# power.net
KiCad netlist of a schematic drawn in Altium Designer
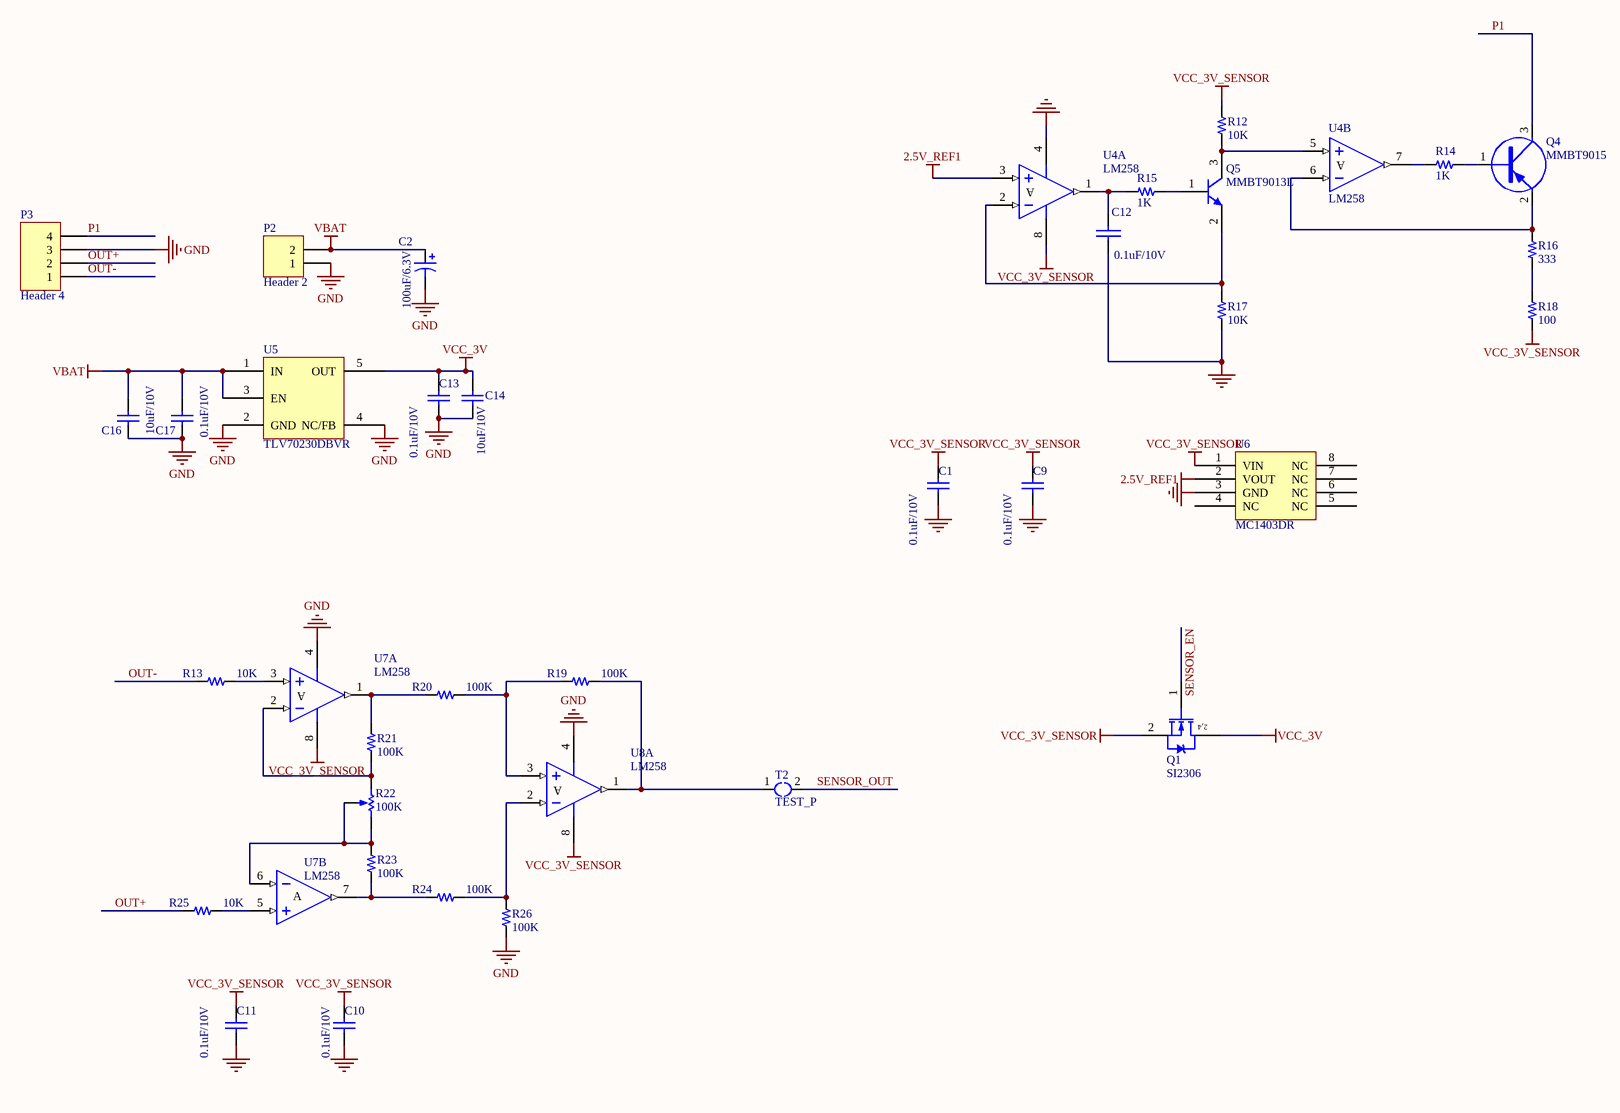
[diagram p0: power.SchDoc]

(export (version "E")
  (design (tool "Eeschema 10.0.6"))
  (components
    (comp (ref "C1")
      (value "0.1uF/10V")
      (footprint "0603C")
      (description "Capacitor")
      (fields (field (name "PUBLISHER") "Altium Limited"))
      (libsource (lib "Miscellaneous Devices") (part "Cap"))
    )
    (comp (ref "C2")
      (value "100uF/6.3V")
      (footprint "7343")
      (description "Polarized Capacitor (Radial)")
      (fields (field (name "PUBLISHER") "Altium Limited"))
      (libsource (lib "Miscellaneous Devices") (part "Cap Pol1"))
    )
    (comp (ref "C9")
      (value "0.1uF/10V")
      (footprint "0603C")
      (description "Capacitor")
      (fields (field (name "PUBLISHER") "Altium Limited"))
      (libsource (lib "Miscellaneous Devices") (part "Cap"))
    )
    (comp (ref "C10")
      (value "0.1uF/10V")
      (footprint "0603C")
      (description "Capacitor")
      (fields (field (name "PUBLISHER") "Altium Limited"))
      (libsource (lib "Miscellaneous Devices") (part "Cap"))
    )
    (comp (ref "C11")
      (value "0.1uF/10V")
      (footprint "0603C")
      (description "Capacitor")
      (fields (field (name "PUBLISHER") "Altium Limited"))
      (libsource (lib "Miscellaneous Devices") (part "Cap"))
    )
    (comp (ref "C12")
      (value "0.1uF/10V")
      (footprint "0603C")
      (description "Capacitor")
      (libsource (lib "*") (part "CAP"))
    )
    (comp (ref "C13")
      (value "0.1uF/10V")
      (footprint "0603C")
      (description "Capacitor")
      (fields (field (name "PUBLISHER") "Altium Limited"))
      (libsource (lib "Miscellaneous Devices") (part "Cap"))
    )
    (comp (ref "C14")
      (value "10uF/10V")
      (footprint "0603C")
      (description "Capacitor")
      (fields (field (name "PUBLISHER") "Altium Limited"))
      (libsource (lib "Miscellaneous Devices") (part "Cap"))
    )
    (comp (ref "C16")
      (value "10uF/10V")
      (footprint "0603C")
      (description "Capacitor")
      (fields (field (name "PUBLISHER") "Altium Limited"))
      (libsource (lib "Miscellaneous Devices") (part "Cap"))
    )
    (comp (ref "C17")
      (value "0.1uF/10V")
      (footprint "0603C")
      (description "Capacitor")
      (fields (field (name "PUBLISHER") "Altium Limited"))
      (libsource (lib "Miscellaneous Devices") (part "Cap"))
    )
    (comp (ref "P2")
      (value "Header 2")
      (footprint "2X2.54MM")
      (description "Header, 2-Pin")
      (fields (field (name "PUBLISHER") "Altium Limited"))
      (libsource (lib "Miscellaneous Connectors") (part "Header 2"))
    )
    (comp (ref "P3")
      (value "Header 4")
      (footprint "HDR1X4")
      (description "Header, 4-Pin")
      (fields (field (name "PUBLISHER") "Altium Limited"))
      (libsource (lib "Miscellaneous Connectors") (part "Header 4"))
    )
    (comp (ref "Q1")
      (value "SI2306")
      (footprint "SOT23-3")
      (description "BUK92150-55A")
      (fields (field (name "PUBLISHER") "Altium Limited"))
      (libsource (lib "Schlib1") (part "BUK92150-55A"))
    )
    (comp (ref "Q4") (value "MMBT9015") (footprint "SOT23-3") (libsource (lib "Schlib1") (part "PNP")))
    (comp (ref "Q5") (value "MMBT9013L") (footprint "SOT23-3") (libsource (lib "Schlib1") (part "NPN")))
    (comp (ref "R12")
      (value "10K")
      (footprint "0603R")
      (description "R")
      (libsource (lib "JRJ_1") (part "R"))
    )
    (comp (ref "R13")
      (value "10K")
      (footprint "0603R")
      (description "R")
      (libsource (lib "JRJ_1") (part "R"))
    )
    (comp (ref "R14") (value "1K") (footprint "0603R") (description "R") (libsource (lib "JRJ_1") (part "R")))
    (comp (ref "R15") (value "1K") (footprint "0603R") (description "R") (libsource (lib "JRJ_1") (part "R")))
    (comp (ref "R16")
      (value "333")
      (footprint "0603R")
      (description "R")
      (libsource (lib "JRJ_1") (part "R"))
    )
    (comp (ref "R17")
      (value "10K")
      (footprint "0603R")
      (description "R")
      (libsource (lib "JRJ_1") (part "R"))
    )
    (comp (ref "R18")
      (value "100")
      (footprint "0603R")
      (description "R")
      (libsource (lib "JRJ_1") (part "R"))
    )
    (comp (ref "R19")
      (value "100K")
      (footprint "0603R")
      (description "R")
      (libsource (lib "JRJ_1") (part "R"))
    )
    (comp (ref "R20")
      (value "100K")
      (footprint "0603R")
      (description "R")
      (libsource (lib "JRJ_1") (part "R"))
    )
    (comp (ref "R21")
      (value "100K")
      (footprint "0603R")
      (description "R")
      (libsource (lib "JRJ_1") (part "R"))
    )
    (comp (ref "R22")
      (value "100K")
      (footprint "HDR1X3")
      (description "Potentiometer")
      (fields (field (name "PUBLISHER") "Altium Limited"))
      (libsource (lib "Miscellaneous Devices") (part "RPot"))
    )
    (comp (ref "R23")
      (value "100K")
      (footprint "0603R")
      (description "R")
      (libsource (lib "JRJ_1") (part "R"))
    )
    (comp (ref "R24")
      (value "100K")
      (footprint "0603R")
      (description "R")
      (libsource (lib "JRJ_1") (part "R"))
    )
    (comp (ref "R25")
      (value "10K")
      (footprint "0603R")
      (description "R")
      (libsource (lib "JRJ_1") (part "R"))
    )
    (comp (ref "R26")
      (value "100K")
      (footprint "0603R")
      (description "R")
      (libsource (lib "JRJ_1") (part "R"))
    )
    (comp (ref "T2")
      (value "TEST_P")
      (footprint "TEST_P")
      (libsource (lib "Schlib_20110825") (part "TEST_P"))
    )
    (comp (ref "U4") (value "LM258") (footprint "so-8") (libsource (lib "Schlib_20110825") (part "LM258")))
    (comp (ref "U5")
      (value "TLV70230DBVR")
      (footprint "SOT23-5(DBV)")
      (libsource (lib "Schlib_20110825") (part "TLV70230DBVR"))
    )
    (comp (ref "U6")
      (value "MC1403DR")
      (footprint "SO-8")
      (libsource (lib "Schlib_20110825") (part "MC1403DR"))
    )
    (comp (ref "U7") (value "LM258") (footprint "so-8") (libsource (lib "Schlib_20110825") (part "LM258")))
    (comp (ref "U8") (value "LM258") (footprint "so-8") (libsource (lib "Schlib_20110825") (part "LM258")))
  )
  (nets
    (net (code "1") (name "/OUT+") (class "Default")
      (node (ref "P3") (pin "2") (pinfunction "2_2") (pintype "passive"))
      (node (ref "R25") (pin "1") (pintype "passive"))
    )
    (net (code "2") (name "/OUT-") (class "Default")
      (node (ref "P3") (pin "1") (pinfunction "1_1") (pintype "passive"))
      (node (ref "R13") (pin "1") (pintype "passive"))
    )
    (net (code "3") (name "/P1") (class "Default")
      (node (ref "P3") (pin "4") (pinfunction "4_4") (pintype "passive"))
      (node (ref "Q4") (pin "3") (pinfunction "C_3") (pintype "passive"))
    )
    (net (code "4") (name "/SENSOR_EN") (class "Default")
      (node (ref "Q1") (pin "1") (pinfunction "G_1") (pintype "passive"))
    )
    (net (code "5") (name "/SENSOR_OUT") (class "Default")
      (node (ref "T2") (pin "2") (pinfunction "2_2") (pintype "passive"))
    )
    (net (code "6") (name "2.5V_REF1") (class "Default")
      (node (ref "U4") (pin "3") (pinfunction "IN+_3") (pintype "input"))
      (node (ref "U6") (pin "2") (pinfunction "VOUT_2") (pintype "passive"))
    )
    (net (code "7") (name "GND") (class "Default")
      (node (ref "C1") (pin "2") (pinfunction "2_2") (pintype "passive"))
      (node (ref "C10") (pin "2") (pinfunction "2_2") (pintype "passive"))
      (node (ref "C11") (pin "2") (pinfunction "2_2") (pintype "passive"))
      (node (ref "C12") (pin "2") (pinfunction "2_2") (pintype "passive"))
      (node (ref "C13") (pin "2") (pinfunction "2_2") (pintype "passive"))
      (node (ref "C14") (pin "1") (pinfunction "1_1") (pintype "passive"))
      (node (ref "C16") (pin "1") (pinfunction "1_1") (pintype "passive"))
      (node (ref "C17") (pin "2") (pinfunction "2_2") (pintype "passive"))
      (node (ref "C2") (pin "2") (pinfunction "2_2") (pintype "passive"))
      (node (ref "C9") (pin "2") (pinfunction "2_2") (pintype "passive"))
      (node (ref "P2") (pin "1") (pinfunction "1_1") (pintype "passive"))
      (node (ref "P3") (pin "3") (pinfunction "3_3") (pintype "passive"))
      (node (ref "R17") (pin "1") (pintype "passive"))
      (node (ref "R26") (pin "1") (pintype "passive"))
      (node (ref "U4") (pin "4") (pinfunction "V-_4") (pintype "power_in"))
      (node (ref "U5") (pin "2") (pinfunction "GND_2") (pintype "passive"))
      (node (ref "U5") (pin "4") (pinfunction "NC/FB_4") (pintype "passive"))
      (node (ref "U6") (pin "3") (pinfunction "GND_3") (pintype "passive"))
      (node (ref "U7") (pin "4") (pinfunction "V-_4") (pintype "power_in"))
      (node (ref "U8") (pin "4") (pinfunction "V-_4") (pintype "power_in"))
    )
    (net (code "8") (name "Net-(Q4-B)") (class "Default")
      (node (ref "Q4") (pin "1") (pinfunction "B_1") (pintype "passive"))
      (node (ref "R14") (pin "2") (pintype "passive"))
    )
    (net (code "9") (name "Net-(Q4-E)") (class "Default")
      (node (ref "Q4") (pin "2") (pinfunction "E_2") (pintype "passive"))
      (node (ref "R16") (pin "2") (pintype "passive"))
      (node (ref "U4") (pin "6") (pinfunction "IN-_6") (pintype "input"))
    )
    (net (code "10") (name "Net-(Q5-B)") (class "Default")
      (node (ref "Q5") (pin "1") (pinfunction "B_1") (pintype "passive"))
      (node (ref "R15") (pin "2") (pintype "passive"))
    )
    (net (code "11") (name "Net-(Q5-C)") (class "Default")
      (node (ref "Q5") (pin "3") (pinfunction "C_3") (pintype "passive"))
      (node (ref "R12") (pin "1") (pintype "passive"))
      (node (ref "U4") (pin "5") (pinfunction "IN+_5") (pintype "input"))
    )
    (net (code "12") (name "Net-(Q5-E)") (class "Default")
      (node (ref "Q5") (pin "2") (pinfunction "E_2") (pintype "passive"))
      (node (ref "R17") (pin "2") (pintype "passive"))
      (node (ref "U4") (pin "2") (pinfunction "IN-_2") (pintype "input"))
    )
    (net (code "13") (name "Net-(R16-Pad1)") (class "Default")
      (node (ref "R16") (pin "1") (pintype "passive"))
      (node (ref "R18") (pin "2") (pintype "passive"))
    )
    (net (code "14") (name "Net-(R22-BOT)") (class "Default")
      (node (ref "R22") (pin "2") (pinfunction "BOT_2") (pintype "passive"))
      (node (ref "R22") (pin "3") (pinfunction "TAP_3") (pintype "passive"))
      (node (ref "R23") (pin "2") (pintype "passive"))
      (node (ref "U7") (pin "6") (pinfunction "IN-_6") (pintype "input"))
    )
    (net (code "15") (name "Net-(R22-TOP)") (class "Default")
      (node (ref "R21") (pin "1") (pintype "passive"))
      (node (ref "R22") (pin "1") (pinfunction "TOP_1") (pintype "passive"))
      (node (ref "U7") (pin "2") (pinfunction "IN-_2") (pintype "input"))
    )
    (net (code "16") (name "Net-(U4A-OUT)") (class "Default")
      (node (ref "C12") (pin "1") (pinfunction "1_1") (pintype "passive"))
      (node (ref "R15") (pin "1") (pintype "passive"))
      (node (ref "U4") (pin "1") (pinfunction "OUT_1") (pintype "output"))
    )
    (net (code "17") (name "Net-(U4B-OUT)") (class "Default")
      (node (ref "R14") (pin "1") (pintype "passive"))
      (node (ref "U4") (pin "7") (pinfunction "OUT_7") (pintype "output"))
    )
    (net (code "18") (name "Net-(U7A-IN+)") (class "Default")
      (node (ref "R13") (pin "2") (pintype "passive"))
      (node (ref "U7") (pin "3") (pinfunction "IN+_3") (pintype "input"))
    )
    (net (code "19") (name "Net-(U7A-OUT)") (class "Default")
      (node (ref "R20") (pin "1") (pintype "passive"))
      (node (ref "R21") (pin "2") (pintype "passive"))
      (node (ref "U7") (pin "1") (pinfunction "OUT_1") (pintype "output"))
    )
    (net (code "20") (name "Net-(U7B-IN+)") (class "Default")
      (node (ref "R25") (pin "2") (pintype "passive"))
      (node (ref "U7") (pin "5") (pinfunction "IN+_5") (pintype "input"))
    )
    (net (code "21") (name "Net-(U7B-OUT)") (class "Default")
      (node (ref "R23") (pin "1") (pintype "passive"))
      (node (ref "R24") (pin "1") (pintype "passive"))
      (node (ref "U7") (pin "7") (pinfunction "OUT_7") (pintype "output"))
    )
    (net (code "22") (name "Net-(U8A-IN+)") (class "Default")
      (node (ref "R19") (pin "1") (pintype "passive"))
      (node (ref "R20") (pin "2") (pintype "passive"))
      (node (ref "U8") (pin "3") (pinfunction "IN+_3") (pintype "input"))
    )
    (net (code "23") (name "Net-(U8A-IN-)") (class "Default")
      (node (ref "R24") (pin "2") (pintype "passive"))
      (node (ref "R26") (pin "2") (pintype "passive"))
      (node (ref "U8") (pin "2") (pinfunction "IN-_2") (pintype "input"))
    )
    (net (code "24") (name "Net-(U8A-OUT)") (class "Default")
      (node (ref "R19") (pin "2") (pintype "passive"))
      (node (ref "T2") (pin "1") (pinfunction "1_1") (pintype "passive"))
      (node (ref "U8") (pin "1") (pinfunction "OUT_1") (pintype "output"))
    )
    (net (code "25") (name "VBAT") (class "Default")
      (node (ref "C16") (pin "2") (pinfunction "2_2") (pintype "passive"))
      (node (ref "C17") (pin "1") (pinfunction "1_1") (pintype "passive"))
      (node (ref "C2") (pin "1") (pinfunction "1_1") (pintype "passive"))
      (node (ref "P2") (pin "2") (pinfunction "2_2") (pintype "passive"))
      (node (ref "U5") (pin "1") (pinfunction "IN_1") (pintype "passive"))
      (node (ref "U5") (pin "3") (pinfunction "EN_3") (pintype "passive"))
    )
    (net (code "26") (name "VCC_3V") (class "Default")
      (node (ref "C13") (pin "1") (pinfunction "1_1") (pintype "passive"))
      (node (ref "C14") (pin "2") (pinfunction "2_2") (pintype "passive"))
      (node (ref "Q1") (pin "3") (pinfunction "D_3") (pintype "passive"))
      (node (ref "U5") (pin "5") (pinfunction "OUT_5") (pintype "passive"))
    )
    (net (code "27") (name "VCC_3V_SENSOR") (class "Default")
      (node (ref "C1") (pin "1") (pinfunction "1_1") (pintype "passive"))
      (node (ref "C10") (pin "1") (pinfunction "1_1") (pintype "passive"))
      (node (ref "C11") (pin "1") (pinfunction "1_1") (pintype "passive"))
      (node (ref "C9") (pin "1") (pinfunction "1_1") (pintype "passive"))
      (node (ref "Q1") (pin "2") (pinfunction "S_2") (pintype "passive"))
      (node (ref "R12") (pin "2") (pintype "passive"))
      (node (ref "R18") (pin "1") (pintype "passive"))
      (node (ref "U4") (pin "8") (pinfunction "V+_8") (pintype "power_in"))
      (node (ref "U6") (pin "1") (pinfunction "VIN_1") (pintype "passive"))
      (node (ref "U7") (pin "8") (pinfunction "V+_8") (pintype "power_in"))
      (node (ref "U8") (pin "8") (pinfunction "V+_8") (pintype "power_in"))
    )
    (net (code "28") (name "unconnected-(U6-NC-Pad4)") (class "Default")
      (node (ref "U6") (pin "4") (pinfunction "NC_4") (pintype "passive"))
    )
    (net (code "29") (name "unconnected-(U6-NC-Pad5)") (class "Default")
      (node (ref "U6") (pin "5") (pinfunction "NC_5") (pintype "passive"))
    )
    (net (code "30") (name "unconnected-(U6-NC-Pad6)") (class "Default")
      (node (ref "U6") (pin "6") (pinfunction "NC_6") (pintype "passive"))
    )
    (net (code "31") (name "unconnected-(U6-NC-Pad7)") (class "Default")
      (node (ref "U6") (pin "7") (pinfunction "NC_7") (pintype "passive"))
    )
    (net (code "32") (name "unconnected-(U6-NC-Pad8)") (class "Default")
      (node (ref "U6") (pin "8") (pinfunction "NC_8") (pintype "passive"))
    )
  )
)
